# STM32_microcontroller_IOs.net
KiCad netlist of a schematic drawn in Altium Designer
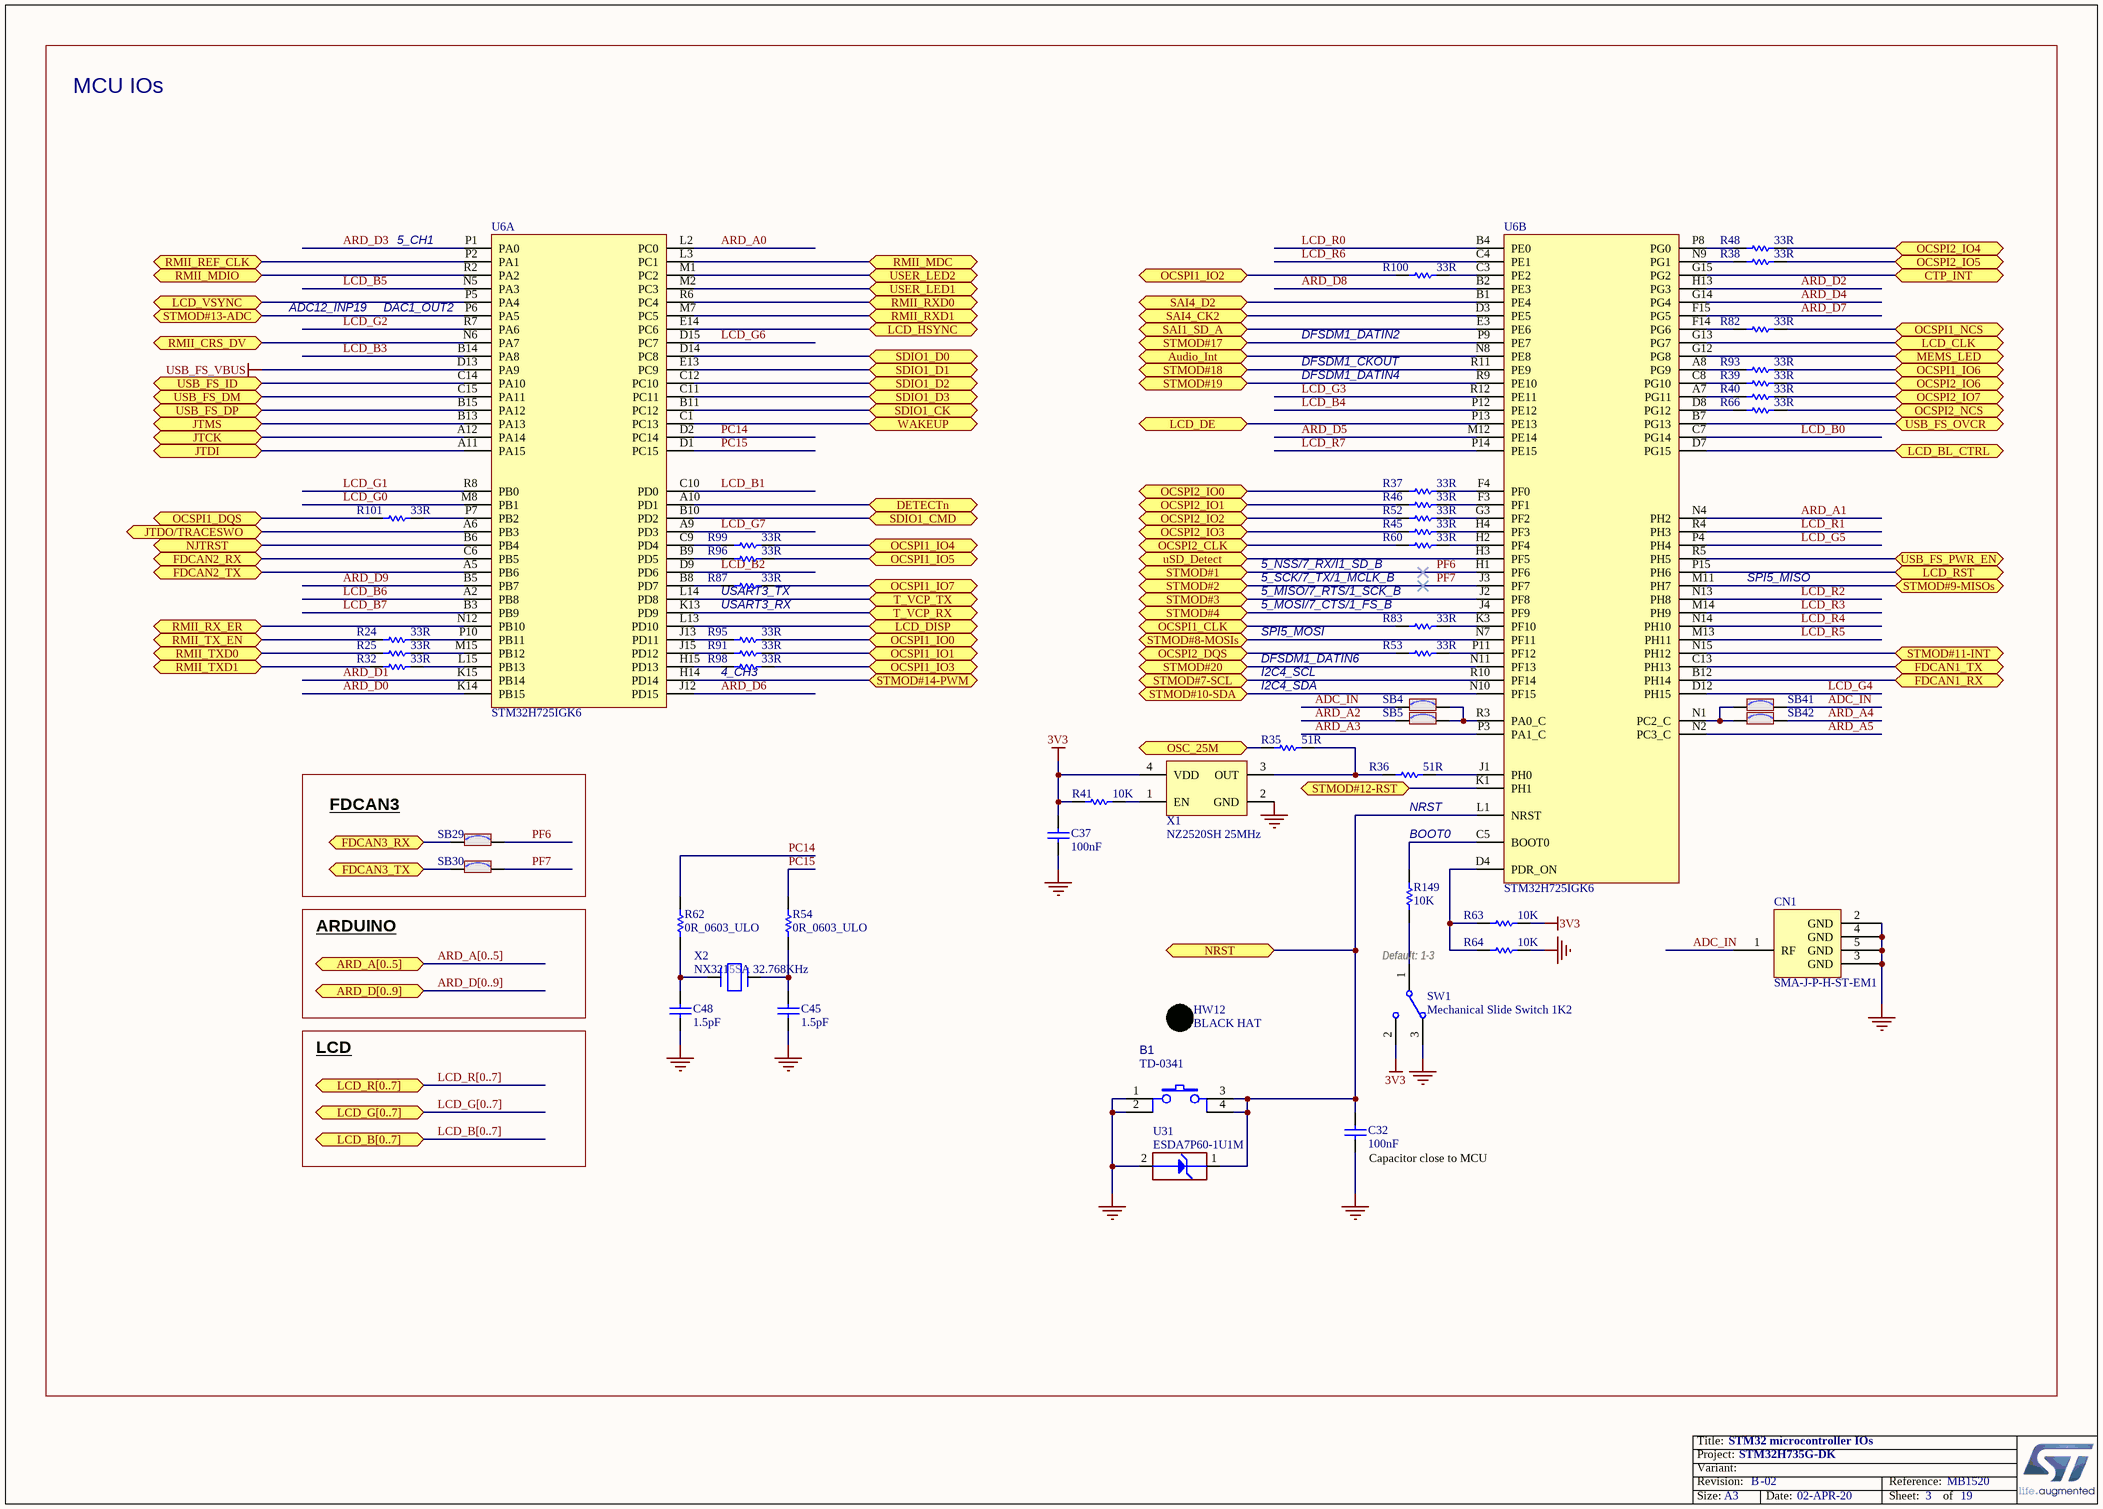
[diagram p0: STM32 microcontroller IOs.SchDoc]

(export (version "E")
  (design (tool "Eeschema 10.0.6"))
  (components
    (comp (ref "B1")
      (value "SW-PUSH-CMS")
      (footprint "SWI_WEALTHMETAL_TD-0341_4P_BLACK")
      (description "Non-Open Push-Button 0.1A 24V BLACK")
      (fields
        (field (name "INTERNAL_PART_NUMBER") "MCD-00001")
        (field (name "MANUFACTURER_PART_NUMBER") "TD-0341")
        (field (name "MANUFACTURER") "WEALTHMETAL")
        (field (name "PROVIDED_BY") "SUBCO")
      )
      (libsource (lib "MCD_PARTS_database") (part "SW-PUSH-CMS"))
    )
    (comp (ref "C32")
      (value "100nF")
      (footprint "C0402")
      (description "Capacitor, MLCC, 100nF, 16V, X7R, 10%, 0402, T=0,5mm")
      (fields
        (field (name "INTERNAL_PART_NUMBER") "MCD-00102")
        (field (name "MANUFACTURER_PART_NUMBER") "CC0402KRX7R7BB104")
        (field (name "PROVIDED_BY") "SUBCO")
      )
      (libsource (lib "MCD_PARTS_database") (part "Capacitor"))
    )
    (comp (ref "C37")
      (value "100nF")
      (footprint "C0402")
      (description "Capacitor, MLCC, 100nF, 16V, X7R, 10%, 0402, T=0,5mm")
      (fields
        (field (name "INTERNAL_PART_NUMBER") "MCD-00102")
        (field (name "MANUFACTURER_PART_NUMBER") "CC0402KRX7R7BB104")
        (field (name "PROVIDED_BY") "SUBCO")
      )
      (libsource (lib "MCD_PARTS_database") (part "Capacitor"))
    )
    (comp (ref "C45")
      (value "1.5pF")
      (footprint "C0402")
      (description "Capacitor, MLCC, 1.5pF, 50V, NPO, +-0.25pF, 0402, T=0,5mm")
      (fields
        (field (name "INTERNAL_PART_NUMBER") "MCD-00563")
        (field (name "MANUFACTURER_PART_NUMBER") "CC0402CRNPO9BN1R5")
        (field (name "PROVIDED_BY") "SUBCO")
      )
      (libsource (lib "MCD_PARTS_database") (part "Capacitor"))
    )
    (comp (ref "C48")
      (value "1.5pF")
      (footprint "C0402")
      (description "Capacitor, MLCC, 1.5pF, 50V, NPO, +-0.25pF, 0402, T=0,5mm")
      (fields
        (field (name "INTERNAL_PART_NUMBER") "MCD-00563")
        (field (name "MANUFACTURER_PART_NUMBER") "CC0402CRNPO9BN1R5")
        (field (name "PROVIDED_BY") "SUBCO")
      )
      (libsource (lib "MCD_PARTS_database") (part "Capacitor"))
    )
    (comp (ref "CN1")
      (value "SMA-J-P-H-ST-EM1")
      (footprint "CON_SAMTEC_SMA-J-P-X-ST-EM1")
      (description "RF SMA connector PCB edge")
      (fields
        (field (name "INTERNAL_PART_NUMBER") "MCD-00279")
        (field (name "MANUFACTURER") "SAMTEC")
        (field (name "PROVIDED_BY") "SUBCO")
      )
      (libsource (lib "MCD_PARTS_database") (part "SMA-J-P-H-ST-EM1"))
    )
    (comp (ref "HW12")
      (value "BLACK HAT")
      (description "Black Hat for switch TD0341X-G01-BLA")
      (fields
        (field (name "INTERNAL_PART_NUMBER") "MCD-00635")
        (field (name "MANUFACTURER_PART_NUMBER") "988.16.09.3.00003_SH-517")
        (field (name "PROVIDED_BY") "SUBCO")
      )
      (libsource (lib "MCD_PARTS_database") (part "BUTTON_HAT_BLACK"))
    )
    (comp (ref "R24")
      (value "33R")
      (footprint "R0402")
      (description "Resistor,33R,0402,1%,1/16W")
      (fields
        (field (name "INTERNAL_PART_NUMBER") "MCD-00455")
        (field (name "MANUFACTURER_PART_NUMBER") "RC0402FR-0733RL")
        (field (name "PROVIDED_BY") "SUBCO")
      )
      (libsource (lib "MCD_PARTS_database") (part "Resistor"))
    )
    (comp (ref "R25")
      (value "33R")
      (footprint "R0402")
      (description "Resistor,33R,0402,1%,1/16W")
      (fields
        (field (name "INTERNAL_PART_NUMBER") "MCD-00455")
        (field (name "MANUFACTURER_PART_NUMBER") "RC0402FR-0733RL")
        (field (name "PROVIDED_BY") "SUBCO")
      )
      (libsource (lib "MCD_PARTS_database") (part "Resistor"))
    )
    (comp (ref "R32")
      (value "33R")
      (footprint "R0402")
      (description "Resistor,33R,0402,1%,1/16W")
      (fields
        (field (name "INTERNAL_PART_NUMBER") "MCD-00455")
        (field (name "MANUFACTURER_PART_NUMBER") "RC0402FR-0733RL")
        (field (name "PROVIDED_BY") "SUBCO")
      )
      (libsource (lib "MCD_PARTS_database") (part "Resistor"))
    )
    (comp (ref "R35")
      (value "51R")
      (footprint "R0402")
      (description "Resistor,51R,0402,1%,1/16W")
      (fields
        (field (name "INTERNAL_PART_NUMBER") "MCD-00485")
        (field (name "MANUFACTURER_PART_NUMBER") "RC0402FR-0751RL")
        (field (name "PROVIDED_BY") "SUBCO")
      )
      (libsource (lib "MCD_PARTS_database") (part "Resistor"))
    )
    (comp (ref "R36")
      (value "51R")
      (footprint "R0402")
      (description "Resistor,51R,0402,1%,1/16W")
      (fields
        (field (name "INTERNAL_PART_NUMBER") "MCD-00485")
        (field (name "MANUFACTURER_PART_NUMBER") "RC0402FR-0751RL")
        (field (name "PROVIDED_BY") "SUBCO")
      )
      (libsource (lib "MCD_PARTS_database") (part "Resistor"))
    )
    (comp (ref "R37")
      (value "33R")
      (footprint "R0402")
      (description "Resistor,33R,0402,1%,1/16W")
      (fields
        (field (name "INTERNAL_PART_NUMBER") "MCD-00455")
        (field (name "MANUFACTURER_PART_NUMBER") "RC0402FR-0733RL")
        (field (name "PROVIDED_BY") "SUBCO")
      )
      (libsource (lib "MCD_PARTS_database") (part "Resistor"))
    )
    (comp (ref "R38")
      (value "33R")
      (footprint "R0402")
      (description "Resistor,33R,0402,1%,1/16W")
      (fields
        (field (name "INTERNAL_PART_NUMBER") "MCD-00455")
        (field (name "MANUFACTURER_PART_NUMBER") "RC0402FR-0733RL")
        (field (name "PROVIDED_BY") "SUBCO")
      )
      (libsource (lib "MCD_PARTS_database") (part "Resistor"))
    )
    (comp (ref "R39")
      (value "33R")
      (footprint "R0402")
      (description "Resistor,33R,0402,1%,1/16W")
      (fields
        (field (name "INTERNAL_PART_NUMBER") "MCD-00455")
        (field (name "MANUFACTURER_PART_NUMBER") "RC0402FR-0733RL")
        (field (name "PROVIDED_BY") "SUBCO")
      )
      (libsource (lib "MCD_PARTS_database") (part "Resistor"))
    )
    (comp (ref "R40")
      (value "33R")
      (footprint "R0402")
      (description "Resistor,33R,0402,1%,1/16W")
      (fields
        (field (name "INTERNAL_PART_NUMBER") "MCD-00455")
        (field (name "MANUFACTURER_PART_NUMBER") "RC0402FR-0733RL")
        (field (name "PROVIDED_BY") "SUBCO")
      )
      (libsource (lib "MCD_PARTS_database") (part "Resistor"))
    )
    (comp (ref "R41")
      (value "10K")
      (footprint "R0402")
      (description "Resistor,10K,0402,1%,1/16W")
      (fields
        (field (name "INTERNAL_PART_NUMBER") "MCD-00053")
        (field (name "MANUFACTURER_PART_NUMBER") "RC0402FR-0710KL")
        (field (name "PROVIDED_BY") "SUBCO")
      )
      (libsource (lib "MCD_PARTS_database") (part "Resistor"))
    )
    (comp (ref "R45")
      (value "33R")
      (footprint "R0402")
      (description "Resistor,33R,0402,1%,1/16W")
      (fields
        (field (name "INTERNAL_PART_NUMBER") "MCD-00455")
        (field (name "MANUFACTURER_PART_NUMBER") "RC0402FR-0733RL")
        (field (name "PROVIDED_BY") "SUBCO")
      )
      (libsource (lib "MCD_PARTS_database") (part "Resistor"))
    )
    (comp (ref "R46")
      (value "33R")
      (footprint "R0402")
      (description "Resistor,33R,0402,1%,1/16W")
      (fields
        (field (name "INTERNAL_PART_NUMBER") "MCD-00455")
        (field (name "MANUFACTURER_PART_NUMBER") "RC0402FR-0733RL")
        (field (name "PROVIDED_BY") "SUBCO")
      )
      (libsource (lib "MCD_PARTS_database") (part "Resistor"))
    )
    (comp (ref "R48")
      (value "33R")
      (footprint "R0402")
      (description "Resistor,33R,0402,1%,1/16W")
      (fields
        (field (name "INTERNAL_PART_NUMBER") "MCD-00455")
        (field (name "MANUFACTURER_PART_NUMBER") "RC0402FR-0733RL")
        (field (name "PROVIDED_BY") "SUBCO")
      )
      (libsource (lib "MCD_PARTS_database") (part "Resistor"))
    )
    (comp (ref "R52")
      (value "33R")
      (footprint "R0402")
      (description "Resistor,33R,0402,1%,1/16W")
      (fields
        (field (name "INTERNAL_PART_NUMBER") "MCD-00455")
        (field (name "MANUFACTURER_PART_NUMBER") "RC0402FR-0733RL")
        (field (name "PROVIDED_BY") "SUBCO")
      )
      (libsource (lib "MCD_PARTS_database") (part "Resistor"))
    )
    (comp (ref "R53")
      (value "33R")
      (footprint "R0402")
      (description "Resistor,33R,0402,1%,1/16W")
      (fields
        (field (name "INTERNAL_PART_NUMBER") "MCD-00455")
        (field (name "MANUFACTURER_PART_NUMBER") "RC0402FR-0733RL")
        (field (name "PROVIDED_BY") "SUBCO")
      )
      (libsource (lib "MCD_PARTS_database") (part "Resistor"))
    )
    (comp (ref "R54")
      (value "0R_0603_ULO")
      (footprint "R0603")
      (description "Resistor,0R,0603,ULO")
      (fields
        (field (name "INTERNAL_PART_NUMBER") "MCD-00181")
        (field (name "MANUFACTURER_PART_NUMBER") "PMR03EZPJ000")
        (field (name "PROVIDED_BY") "SUBCO")
      )
      (libsource (lib "MCD_PARTS_database") (part "Resistor"))
    )
    (comp (ref "R60")
      (value "33R")
      (footprint "R0402")
      (description "Resistor,33R,0402,1%,1/16W")
      (fields
        (field (name "INTERNAL_PART_NUMBER") "MCD-00455")
        (field (name "MANUFACTURER_PART_NUMBER") "RC0402FR-0733RL")
        (field (name "PROVIDED_BY") "SUBCO")
      )
      (libsource (lib "MCD_PARTS_database") (part "Resistor"))
    )
    (comp (ref "R62")
      (value "0R_0603_ULO")
      (footprint "R0603")
      (description "Resistor,0R,0603,ULO")
      (fields
        (field (name "INTERNAL_PART_NUMBER") "MCD-00181")
        (field (name "MANUFACTURER_PART_NUMBER") "PMR03EZPJ000")
        (field (name "PROVIDED_BY") "SUBCO")
      )
      (libsource (lib "MCD_PARTS_database") (part "Resistor"))
    )
    (comp (ref "R63")
      (value "10K")
      (footprint "R0402")
      (description "Resistor,10K,0402,1%,1/16W")
      (fields
        (field (name "INTERNAL_PART_NUMBER") "MCD-00053")
        (field (name "MANUFACTURER_PART_NUMBER") "RC0402FR-0710KL")
        (field (name "PROVIDED_BY") "SUBCO")
      )
      (libsource (lib "MCD_PARTS_database") (part "Resistor"))
    )
    (comp (ref "R64")
      (value "10K")
      (footprint "R0402")
      (description "Resistor,10K,0402,1%,1/16W")
      (fields
        (field (name "INTERNAL_PART_NUMBER") "MCD-00053")
        (field (name "MANUFACTURER_PART_NUMBER") "RC0402FR-0710KL")
        (field (name "PROVIDED_BY") "SUBCO")
      )
      (libsource (lib "MCD_PARTS_database") (part "Resistor"))
    )
    (comp (ref "R66")
      (value "33R")
      (footprint "R0402")
      (description "Resistor,33R,0402,1%,1/16W")
      (fields
        (field (name "INTERNAL_PART_NUMBER") "MCD-00455")
        (field (name "MANUFACTURER_PART_NUMBER") "RC0402FR-0733RL")
        (field (name "PROVIDED_BY") "SUBCO")
      )
      (libsource (lib "MCD_PARTS_database") (part "Resistor"))
    )
    (comp (ref "R82")
      (value "33R")
      (footprint "R0402")
      (description "Resistor,33R,0402,1%,1/16W")
      (fields
        (field (name "INTERNAL_PART_NUMBER") "MCD-00455")
        (field (name "MANUFACTURER_PART_NUMBER") "RC0402FR-0733RL")
        (field (name "PROVIDED_BY") "SUBCO")
      )
      (libsource (lib "MCD_PARTS_database") (part "Resistor"))
    )
    (comp (ref "R83")
      (value "33R")
      (footprint "R0402")
      (description "Resistor,33R,0402,1%,1/16W")
      (fields
        (field (name "INTERNAL_PART_NUMBER") "MCD-00455")
        (field (name "MANUFACTURER_PART_NUMBER") "RC0402FR-0733RL")
        (field (name "PROVIDED_BY") "SUBCO")
      )
      (libsource (lib "MCD_PARTS_database") (part "Resistor"))
    )
    (comp (ref "R87")
      (value "33R")
      (footprint "R0402")
      (description "Resistor,33R,0402,1%,1/16W")
      (fields
        (field (name "INTERNAL_PART_NUMBER") "MCD-00455")
        (field (name "MANUFACTURER_PART_NUMBER") "RC0402FR-0733RL")
        (field (name "PROVIDED_BY") "SUBCO")
      )
      (libsource (lib "MCD_PARTS_database") (part "Resistor"))
    )
    (comp (ref "R91")
      (value "33R")
      (footprint "R0402")
      (description "Resistor,33R,0402,1%,1/16W")
      (fields
        (field (name "INTERNAL_PART_NUMBER") "MCD-00455")
        (field (name "MANUFACTURER_PART_NUMBER") "RC0402FR-0733RL")
        (field (name "PROVIDED_BY") "SUBCO")
      )
      (libsource (lib "MCD_PARTS_database") (part "Resistor"))
    )
    (comp (ref "R93")
      (value "33R")
      (footprint "R0402")
      (description "Resistor,33R,0402,1%,1/16W")
      (fields
        (field (name "INTERNAL_PART_NUMBER") "MCD-00455")
        (field (name "MANUFACTURER_PART_NUMBER") "RC0402FR-0733RL")
        (field (name "PROVIDED_BY") "SUBCO")
      )
      (libsource (lib "MCD_PARTS_database") (part "Resistor"))
    )
    (comp (ref "R95")
      (value "33R")
      (footprint "R0402")
      (description "Resistor,33R,0402,1%,1/16W")
      (fields
        (field (name "INTERNAL_PART_NUMBER") "MCD-00455")
        (field (name "MANUFACTURER_PART_NUMBER") "RC0402FR-0733RL")
        (field (name "PROVIDED_BY") "SUBCO")
      )
      (libsource (lib "MCD_PARTS_database") (part "Resistor"))
    )
    (comp (ref "R96")
      (value "33R")
      (footprint "R0402")
      (description "Resistor,33R,0402,1%,1/16W")
      (fields
        (field (name "INTERNAL_PART_NUMBER") "MCD-00455")
        (field (name "MANUFACTURER_PART_NUMBER") "RC0402FR-0733RL")
        (field (name "PROVIDED_BY") "SUBCO")
      )
      (libsource (lib "MCD_PARTS_database") (part "Resistor"))
    )
    (comp (ref "R98")
      (value "33R")
      (footprint "R0402")
      (description "Resistor,33R,0402,1%,1/16W")
      (fields
        (field (name "INTERNAL_PART_NUMBER") "MCD-00455")
        (field (name "MANUFACTURER_PART_NUMBER") "RC0402FR-0733RL")
        (field (name "PROVIDED_BY") "SUBCO")
      )
      (libsource (lib "MCD_PARTS_database") (part "Resistor"))
    )
    (comp (ref "R99")
      (value "33R")
      (footprint "R0402")
      (description "Resistor,33R,0402,1%,1/16W")
      (fields
        (field (name "INTERNAL_PART_NUMBER") "MCD-00455")
        (field (name "MANUFACTURER_PART_NUMBER") "RC0402FR-0733RL")
        (field (name "PROVIDED_BY") "SUBCO")
      )
      (libsource (lib "MCD_PARTS_database") (part "Resistor"))
    )
    (comp (ref "R100")
      (value "33R")
      (footprint "R0402")
      (description "Resistor,33R,0402,1%,1/16W")
      (fields
        (field (name "INTERNAL_PART_NUMBER") "MCD-00455")
        (field (name "MANUFACTURER_PART_NUMBER") "RC0402FR-0733RL")
        (field (name "PROVIDED_BY") "SUBCO")
      )
      (libsource (lib "MCD_PARTS_database") (part "Resistor"))
    )
    (comp (ref "R101")
      (value "33R")
      (footprint "R0402")
      (description "Resistor,33R,0402,1%,1/16W")
      (fields
        (field (name "INTERNAL_PART_NUMBER") "MCD-00455")
        (field (name "MANUFACTURER_PART_NUMBER") "RC0402FR-0733RL")
        (field (name "PROVIDED_BY") "SUBCO")
      )
      (libsource (lib "MCD_PARTS_database") (part "Resistor"))
    )
    (comp (ref "R149")
      (value "10K")
      (footprint "R0402")
      (description "Resistor,10K,0402,1%,1/16W")
      (fields
        (field (name "INTERNAL_PART_NUMBER") "MCD-00053")
        (field (name "MANUFACTURER_PART_NUMBER") "RC0402FR-0710KL")
        (field (name "PROVIDED_BY") "SUBCO")
      )
      (libsource (lib "MCD_PARTS_database") (part "Resistor"))
    )
    (comp (ref "SB4")
      (value "SB_ON")
      (footprint "SOLDER-BRIDGE_R0603-0R")
      (description "Solder Bridge ON")
      (fields
        (field (name "INTERNAL_PART_NUMBER") "MCD-00071")
        (field (name "MANUFACTURER_PART_NUMBER") "RC0603JR-070RL")
        (field (name "PROVIDED_BY") "SUBCO")
      )
      (libsource (lib "MCD_PARTS_database") (part "SB_ON"))
    )
    (comp (ref "SB5")
      (value "SB_ON")
      (footprint "SOLDER-BRIDGE_R0603-0R")
      (description "Solder Bridge ON")
      (fields
        (field (name "INTERNAL_PART_NUMBER") "MCD-00071")
        (field (name "MANUFACTURER_PART_NUMBER") "RC0603JR-070RL")
        (field (name "PROVIDED_BY") "SUBCO")
      )
      (libsource (lib "MCD_PARTS_database") (part "SB_ON"))
    )
    (comp (ref "SB29")
      (value "SB_ON")
      (footprint "SOLDER-BRIDGE_R0603-0R")
      (description "Solder Bridge ON")
      (fields
        (field (name "INTERNAL_PART_NUMBER") "MCD-00071")
        (field (name "MANUFACTURER_PART_NUMBER") "RC0603JR-070RL")
        (field (name "PROVIDED_BY") "SUBCO")
      )
      (libsource (lib "MCD_PARTS_database") (part "SB_ON"))
    )
    (comp (ref "SB30")
      (value "SB_ON")
      (footprint "SOLDER-BRIDGE_R0603-0R")
      (description "Solder Bridge ON")
      (fields
        (field (name "INTERNAL_PART_NUMBER") "MCD-00071")
        (field (name "MANUFACTURER_PART_NUMBER") "RC0603JR-070RL")
        (field (name "PROVIDED_BY") "SUBCO")
      )
      (libsource (lib "MCD_PARTS_database") (part "SB_ON"))
    )
    (comp (ref "SB41")
      (value "SB_ON")
      (footprint "SOLDER-BRIDGE_R0603-0R")
      (description "Solder Bridge ON")
      (fields
        (field (name "INTERNAL_PART_NUMBER") "MCD-00071")
        (field (name "MANUFACTURER_PART_NUMBER") "RC0603JR-070RL")
        (field (name "PROVIDED_BY") "SUBCO")
      )
      (libsource (lib "MCD_PARTS_database") (part "SB_ON"))
    )
    (comp (ref "SB42")
      (value "SB_ON")
      (footprint "SOLDER-BRIDGE_R0603-0R")
      (description "Solder Bridge ON")
      (fields
        (field (name "INTERNAL_PART_NUMBER") "MCD-00071")
        (field (name "MANUFACTURER_PART_NUMBER") "RC0603JR-070RL")
        (field (name "PROVIDED_BY") "SUBCO")
      )
      (libsource (lib "MCD_PARTS_database") (part "SB_ON"))
    )
    (comp (ref "SW1")
      (value "Mechanical Slide Switch 1K2")
      (footprint "SWI_EAO_09-03290-01_EXTENDED_STRAIGHT_BLACK")
      (description "Mechanical Slide Switches 1K2 BLK ACT GOLD STRT MNT")
      (fields
        (field (name "INTERNAL_PART_NUMBER") "MCD-00566")
        (field (name "MANUFACTURER_PART_NUMBER") "09.03290.01")
        (field (name "PROVIDED_BY") "SUBCO")
      )
      (libsource (lib "MCD_PARTS_database") (part "SW_MECA_1K2"))
    )
    (comp (ref "U6")
      (value "STM32H725IGK6")
      (footprint "ICC_UFBGA201_176+25_10X10_P065")
      (description "STM32H725IGK6 MCU, Cut1.0, 10x10x0.6mm, Pitch0.65mm, Int SMPS")
      (fields
        (field (name "INTERNAL_PART_NUMBER") "MCD-01673")
        (field (name "MANUFACTURER") "STMICROELECTRONICS")
        (field (name "PROVIDED_BY") "SUBCO with ST control")
      )
      (libsource (lib "MCD_PARTS_database") (part "STM32H725IGK6U"))
    )
    (comp (ref "U31")
      (value "ESDA7P60-1U1M")
      (footprint "ESD_QFN2_1P6X1_P125")
      (description "High power transient voltage suppressor, 7V breakdown")
      (fields
        (field (name "INTERNAL_PART_NUMBER") "MCD-00251")
        (field (name "MANUFACTURER") "STMICROELECTRONICS")
        (field (name "PROVIDED_BY") "SUBCO with ST control")
      )
      (libsource (lib "MCD_PARTS_database") (part "ESD-TRANSIL"))
    )
    (comp (ref "X1")
      (value "NZ2520SH 25MHz")
      (footprint "OSC_NDK_NZ2520SB_4P")
      (description "Oscillator 25Mhz, +-50ppm, Vcc:3.3V typ, square wave: [0.1Vcc;0.9Vcc], Enable pin, SMD")
      (fields
        (field (name "INTERNAL_PART_NUMBER") "MCD-00597")
        (field (name "MANUFACTURER_PART_NUMBER") "NZ2520SH 25MHz END4869C")
        (field (name "PROVIDED_BY") "SUBCO")
      )
      (libsource (lib "MCD_PARTS_database") (part "OSCILLATOR_4_PINS"))
    )
    (comp (ref "X2")
      (value "NX3215SA 32.768KHz")
      (footprint "CRY_NX3215SA_2P")
      (description "Crystal 32.768kHz, 6pF, +-20ppm, 50Kohms max, SMD")
      (fields
        (field (name "INTERNAL_PART_NUMBER") "MCD-00091")
        (field (name "MANUFACTURER_PART_NUMBER") "NX3215SA 32.768KHz EXS00A-MU00525")
        (field (name "PROVIDED_BY") "SUBCO")
      )
      (libsource (lib "MCD_PARTS_database") (part "XTAL_2_PINS"))
    )
  )
  (nets
    (net (code "1") (name "/ADC_IN") (class "Default")
      (node (ref "CN1") (pin "1") (pinfunction "RF_1") (pintype "passive"))
      (node (ref "SB4") (pin "1") (pinfunction "1_1") (pintype "passive"))
      (node (ref "SB41") (pin "2") (pinfunction "2_2") (pintype "passive"))
    )
    (net (code "2") (name "/ARD_A0") (class "Default")
      (node (ref "U6") (pin "L2") (pinfunction "PC0_L2") (pintype "passive"))
    )
    (net (code "3") (name "/ARD_A1") (class "Default")
      (node (ref "U6") (pin "N4") (pinfunction "PH2_N4") (pintype "passive"))
    )
    (net (code "4") (name "/ARD_A2") (class "Default")
      (node (ref "SB5") (pin "1") (pinfunction "1_1") (pintype "passive"))
    )
    (net (code "5") (name "/ARD_A3") (class "Default")
      (node (ref "U6") (pin "P3") (pinfunction "PA1_C_P3") (pintype "passive"))
    )
    (net (code "6") (name "/ARD_A4") (class "Default")
      (node (ref "SB42") (pin "2") (pinfunction "2_2") (pintype "passive"))
    )
    (net (code "7") (name "/ARD_A5") (class "Default")
      (node (ref "U6") (pin "N2") (pinfunction "PC3_C_N2") (pintype "passive"))
    )
    (net (code "9") (name "/ARD_D0") (class "Default")
      (node (ref "U6") (pin "K14") (pinfunction "PB15_K14") (pintype "passive"))
    )
    (net (code "10") (name "/ARD_D1") (class "Default")
      (node (ref "U6") (pin "K15") (pinfunction "PB14_K15") (pintype "passive"))
    )
    (net (code "11") (name "/ARD_D2") (class "Default")
      (node (ref "U6") (pin "H13") (pinfunction "PG3_H13") (pintype "passive"))
    )
    (net (code "12") (name "/ARD_D3") (class "Default")
      (node (ref "U6") (pin "P1") (pinfunction "PA0_P1") (pintype "passive"))
    )
    (net (code "13") (name "/ARD_D4") (class "Default")
      (node (ref "U6") (pin "G14") (pinfunction "PG4_G14") (pintype "passive"))
    )
    (net (code "14") (name "/ARD_D5") (class "Default")
      (node (ref "U6") (pin "M12") (pinfunction "PE14_M12") (pintype "passive"))
    )
    (net (code "15") (name "/ARD_D6") (class "Default")
      (node (ref "U6") (pin "J12") (pinfunction "PD15_J12") (pintype "passive"))
    )
    (net (code "16") (name "/ARD_D7") (class "Default")
      (node (ref "U6") (pin "F15") (pinfunction "PG5_F15") (pintype "passive"))
    )
    (net (code "17") (name "/ARD_D8") (class "Default")
      (node (ref "U6") (pin "B2") (pinfunction "PE3_B2") (pintype "passive"))
    )
    (net (code "18") (name "/ARD_D9") (class "Default")
      (node (ref "U6") (pin "B5") (pinfunction "PB7_B5") (pintype "passive"))
    )
    (net (code "20") (name "/Audio_Int") (class "Default")
      (node (ref "U6") (pin "N8") (pinfunction "PE8_N8") (pintype "passive"))
    )
    (net (code "21") (name "/CTP_INT") (class "Default")
      (node (ref "U6") (pin "G15") (pinfunction "PG2_G15") (pintype "passive"))
    )
    (net (code "22") (name "/DETECTn") (class "Default")
      (node (ref "U6") (pin "A10") (pinfunction "PD1_A10") (pintype "passive"))
    )
    (net (code "23") (name "/FDCAN1_RX") (class "Default")
      (node (ref "U6") (pin "B12") (pinfunction "PH14_B12") (pintype "passive"))
    )
    (net (code "24") (name "/FDCAN1_TX") (class "Default")
      (node (ref "U6") (pin "C13") (pinfunction "PH13_C13") (pintype "passive"))
    )
    (net (code "25") (name "/FDCAN2_RX") (class "Default")
      (node (ref "U6") (pin "C6") (pinfunction "PB5_C6") (pintype "passive"))
    )
    (net (code "26") (name "/FDCAN2_TX") (class "Default")
      (node (ref "U6") (pin "A5") (pinfunction "PB6_A5") (pintype "passive"))
    )
    (net (code "27") (name "/FDCAN3_RX") (class "Default")
      (node (ref "SB29") (pin "1") (pinfunction "1_1") (pintype "passive"))
    )
    (net (code "28") (name "/FDCAN3_TX") (class "Default")
      (node (ref "SB30") (pin "1") (pinfunction "1_1") (pintype "passive"))
    )
    (net (code "29") (name "/JTCK") (class "Default")
      (node (ref "U6") (pin "A12") (pinfunction "PA14_A12") (pintype "passive"))
    )
    (net (code "30") (name "/JTDI") (class "Default")
      (node (ref "U6") (pin "A11") (pinfunction "PA15_A11") (pintype "passive"))
    )
    (net (code "31") (name "/JTDO{slash}TRACESWO") (class "Default")
      (node (ref "U6") (pin "A6") (pinfunction "PB3_A6") (pintype "passive"))
    )
    (net (code "32") (name "/JTMS") (class "Default")
      (node (ref "U6") (pin "B13") (pinfunction "PA13_B13") (pintype "passive"))
    )
    (net (code "33") (name "/LCD_B0") (class "Default")
      (node (ref "U6") (pin "C7") (pinfunction "PG14_C7") (pintype "passive"))
    )
    (net (code "34") (name "/LCD_B1") (class "Default")
      (node (ref "U6") (pin "C10") (pinfunction "PD0_C10") (pintype "passive"))
    )
    (net (code "35") (name "/LCD_B2") (class "Default")
      (node (ref "U6") (pin "D9") (pinfunction "PD6_D9") (pintype "passive"))
    )
    (net (code "36") (name "/LCD_B3") (class "Default")
      (node (ref "U6") (pin "B14") (pinfunction "PA8_B14") (pintype "passive"))
    )
    (net (code "37") (name "/LCD_B4") (class "Default")
      (node (ref "U6") (pin "P12") (pinfunction "PE12_P12") (pintype "passive"))
    )
    (net (code "38") (name "/LCD_B5") (class "Default")
      (node (ref "U6") (pin "N5") (pinfunction "PA3_N5") (pintype "passive"))
    )
    (net (code "39") (name "/LCD_B6") (class "Default")
      (node (ref "U6") (pin "A2") (pinfunction "PB8_A2") (pintype "passive"))
    )
    (net (code "40") (name "/LCD_B7") (class "Default")
      (node (ref "U6") (pin "B3") (pinfunction "PB9_B3") (pintype "passive"))
    )
    (net (code "41") (name "/LCD_BL_CTRL") (class "Default")
      (node (ref "U6") (pin "D7") (pinfunction "PG15_D7") (pintype "passive"))
    )
    (net (code "43") (name "/LCD_CLK") (class "Default")
      (node (ref "U6") (pin "G13") (pinfunction "PG7_G13") (pintype "passive"))
    )
    (net (code "44") (name "/LCD_DE") (class "Default")
      (node (ref "U6") (pin "P13") (pinfunction "PE13_P13") (pintype "passive"))
    )
    (net (code "45") (name "/LCD_DISP") (class "Default")
      (node (ref "U6") (pin "L13") (pinfunction "PD10_L13") (pintype "passive"))
    )
    (net (code "46") (name "/LCD_G0") (class "Default")
      (node (ref "U6") (pin "M8") (pinfunction "PB1_M8") (pintype "passive"))
    )
    (net (code "47") (name "/LCD_G1") (class "Default")
      (node (ref "U6") (pin "R8") (pinfunction "PB0_R8") (pintype "passive"))
    )
    (net (code "48") (name "/LCD_G2") (class "Default")
      (node (ref "U6") (pin "R7") (pinfunction "PA6_R7") (pintype "passive"))
    )
    (net (code "49") (name "/LCD_G3") (class "Default")
      (node (ref "U6") (pin "R12") (pinfunction "PE11_R12") (pintype "passive"))
    )
    (net (code "50") (name "/LCD_G4") (class "Default")
      (node (ref "U6") (pin "D12") (pinfunction "PH15_D12") (pintype "passive"))
    )
    (net (code "51") (name "/LCD_G5") (class "Default")
      (node (ref "U6") (pin "P4") (pinfunction "PH4_P4") (pintype "passive"))
    )
    (net (code "52") (name "/LCD_G6") (class "Default")
      (node (ref "U6") (pin "D15") (pinfunction "PC7_D15") (pintype "passive"))
    )
    (net (code "53") (name "/LCD_G7") (class "Default")
      (node (ref "U6") (pin "A9") (pinfunction "PD3_A9") (pintype "passive"))
    )
    (net (code "55") (name "/LCD_HSYNC") (class "Default")
      (node (ref "U6") (pin "E14") (pinfunction "PC6_E14") (pintype "passive"))
    )
    (net (code "56") (name "/LCD_R0") (class "Default")
      (node (ref "U6") (pin "B4") (pinfunction "PE0_B4") (pintype "passive"))
    )
    (net (code "57") (name "/LCD_R1") (class "Default")
      (node (ref "U6") (pin "R4") (pinfunction "PH3_R4") (pintype "passive"))
    )
    (net (code "58") (name "/LCD_R2") (class "Default")
      (node (ref "U6") (pin "N13") (pinfunction "PH8_N13") (pintype "passive"))
    )
    (net (code "59") (name "/LCD_R3") (class "Default")
      (node (ref "U6") (pin "M14") (pinfunction "PH9_M14") (pintype "passive"))
    )
    (net (code "60") (name "/LCD_R4") (class "Default")
      (node (ref "U6") (pin "N14") (pinfunction "PH10_N14") (pintype "passive"))
    )
    (net (code "61") (name "/LCD_R5") (class "Default")
      (node (ref "U6") (pin "M13") (pinfunction "PH11_M13") (pintype "passive"))
    )
    (net (code "62") (name "/LCD_R6") (class "Default")
      (node (ref "U6") (pin "C4") (pinfunction "PE1_C4") (pintype "passive"))
    )
    (net (code "63") (name "/LCD_R7") (class "Default")
      (node (ref "U6") (pin "P14") (pinfunction "PE15_P14") (pintype "passive"))
    )
    (net (code "64") (name "/LCD_RST") (class "Default")
      (node (ref "U6") (pin "P15") (pinfunction "PH6_P15") (pintype "passive"))
    )
    (net (code "66") (name "/LCD_VSYNC") (class "Default")
      (node (ref "U6") (pin "P5") (pinfunction "PA4_P5") (pintype "passive"))
    )
    (net (code "67") (name "/MEMS_LED") (class "Default")
      (node (ref "U6") (pin "G12") (pinfunction "PG8_G12") (pintype "passive"))
    )
    (net (code "68") (name "/NJTRST") (class "Default")
      (node (ref "U6") (pin "B6") (pinfunction "PB4_B6") (pintype "passive"))
    )
    (net (code "69") (name "/NRST") (class "Default")
      (node (ref "B1") (pin "3") (pinfunction "3_3") (pintype "passive"))
      (node (ref "B1") (pin "4") (pinfunction "4_4") (pintype "passive"))
      (node (ref "C32") (pin "2") (pinfunction "2_2") (pintype "passive"))
      (node (ref "U31") (pin "1") (pinfunction "IO1_1") (pintype "passive"))
      (node (ref "U6") (pin "L1") (pinfunction "NRST_L1") (pintype "passive"))
    )
    (net (code "70") (name "/OCSPI1_CLK") (class "Default")
      (node (ref "R83") (pin "1") (pinfunction "1_1") (pintype "passive"))
    )
    (net (code "71") (name "/OCSPI1_DQS") (class "Default")
      (node (ref "R101") (pin "1") (pinfunction "1_1") (pintype "passive"))
    )
    (net (code "72") (name "/OCSPI1_IO0") (class "Default")
      (node (ref "R95") (pin "2") (pinfunction "2_2") (pintype "passive"))
    )
    (net (code "73") (name "/OCSPI1_IO1") (class "Default")
      (node (ref "R91") (pin "2") (pinfunction "2_2") (pintype "passive"))
    )
    (net (code "74") (name "/OCSPI1_IO2") (class "Default")
      (node (ref "R100") (pin "1") (pinfunction "1_1") (pintype "passive"))
    )
    (net (code "75") (name "/OCSPI1_IO3") (class "Default")
      (node (ref "R98") (pin "2") (pinfunction "2_2") (pintype "passive"))
    )
    (net (code "76") (name "/OCSPI1_IO4") (class "Default")
      (node (ref "R99") (pin "2") (pinfunction "2_2") (pintype "passive"))
    )
    (net (code "77") (name "/OCSPI1_IO5") (class "Default")
      (node (ref "R96") (pin "2") (pinfunction "2_2") (pintype "passive"))
    )
    (net (code "78") (name "/OCSPI1_IO6") (class "Default")
      (node (ref "R93") (pin "2") (pinfunction "2_2") (pintype "passive"))
    )
    (net (code "79") (name "/OCSPI1_IO7") (class "Default")
      (node (ref "R87") (pin "2") (pinfunction "2_2") (pintype "passive"))
    )
    (net (code "80") (name "/OCSPI1_NCS") (class "Default")
      (node (ref "R82") (pin "2") (pinfunction "2_2") (pintype "passive"))
    )
    (net (code "81") (name "/OCSPI2_CLK") (class "Default")
      (node (ref "R60") (pin "1") (pinfunction "1_1") (pintype "passive"))
    )
    (net (code "82") (name "/OCSPI2_DQS") (class "Default")
      (node (ref "R53") (pin "1") (pinfunction "1_1") (pintype "passive"))
    )
    (net (code "83") (name "/OCSPI2_IO0") (class "Default")
      (node (ref "R37") (pin "1") (pinfunction "1_1") (pintype "passive"))
    )
    (net (code "84") (name "/OCSPI2_IO1") (class "Default")
      (node (ref "R46") (pin "1") (pinfunction "1_1") (pintype "passive"))
    )
    (net (code "85") (name "/OCSPI2_IO2") (class "Default")
      (node (ref "R52") (pin "1") (pinfunction "1_1") (pintype "passive"))
    )
    (net (code "86") (name "/OCSPI2_IO3") (class "Default")
      (node (ref "R45") (pin "1") (pinfunction "1_1") (pintype "passive"))
    )
    (net (code "87") (name "/OCSPI2_IO4") (class "Default")
      (node (ref "R48") (pin "2") (pinfunction "2_2") (pintype "passive"))
    )
    (net (code "88") (name "/OCSPI2_IO5") (class "Default")
      (node (ref "R38") (pin "2") (pinfunction "2_2") (pintype "passive"))
    )
    (net (code "89") (name "/OCSPI2_IO6") (class "Default")
      (node (ref "R39") (pin "2") (pinfunction "2_2") (pintype "passive"))
    )
    (net (code "90") (name "/OCSPI2_IO7") (class "Default")
      (node (ref "R40") (pin "2") (pinfunction "2_2") (pintype "passive"))
    )
    (net (code "91") (name "/OCSPI2_NCS") (class "Default")
      (node (ref "R66") (pin "2") (pinfunction "2_2") (pintype "passive"))
    )
    (net (code "92") (name "/OSC_25M") (class "Default")
      (node (ref "R35") (pin "1") (pinfunction "1_1") (pintype "passive"))
    )
    (net (code "93") (name "/PC14") (class "Default")
      (node (ref "R62") (pin "1") (pinfunction "1_1") (pintype "passive"))
      (node (ref "U6") (pin "D2") (pinfunction "PC14_D2") (pintype "passive"))
    )
    (net (code "94") (name "/PC15") (class "Default")
      (node (ref "R54") (pin "1") (pinfunction "1_1") (pintype "passive"))
      (node (ref "U6") (pin "D1") (pinfunction "PC15_D1") (pintype "passive"))
    )
    (net (code "95") (name "/PF6") (class "Default")
      (node (ref "SB29") (pin "2") (pinfunction "2_2") (pintype "passive"))
      (node (ref "U6") (pin "H1") (pinfunction "PF6_H1") (pintype "passive"))
    )
    (net (code "96") (name "/PF7") (class "Default")
      (node (ref "SB30") (pin "2") (pinfunction "2_2") (pintype "passive"))
      (node (ref "U6") (pin "J3") (pinfunction "PF7_J3") (pintype "passive"))
    )
    (net (code "97") (name "/RMII_CRS_DV") (class "Default")
      (node (ref "U6") (pin "N6") (pinfunction "PA7_N6") (pintype "passive"))
    )
    (net (code "98") (name "/RMII_MDC") (class "Default")
      (node (ref "U6") (pin "L3") (pinfunction "PC1_L3") (pintype "passive"))
    )
    (net (code "99") (name "/RMII_MDIO") (class "Default")
      (node (ref "U6") (pin "R2") (pinfunction "PA2_R2") (pintype "passive"))
    )
    (net (code "100") (name "/RMII_REF_CLK") (class "Default")
      (node (ref "U6") (pin "P2") (pinfunction "PA1_P2") (pintype "passive"))
    )
    (net (code "101") (name "/RMII_RXD0") (class "Default")
      (node (ref "U6") (pin "R6") (pinfunction "PC4_R6") (pintype "passive"))
    )
    (net (code "102") (name "/RMII_RXD1") (class "Default")
      (node (ref "U6") (pin "M7") (pinfunction "PC5_M7") (pintype "passive"))
    )
    (net (code "103") (name "/RMII_RX_ER") (class "Default")
      (node (ref "U6") (pin "N12") (pinfunction "PB10_N12") (pintype "passive"))
    )
    (net (code "104") (name "/RMII_TXD0") (class "Default")
      (node (ref "R25") (pin "1") (pinfunction "1_1") (pintype "passive"))
    )
    (net (code "105") (name "/RMII_TXD1") (class "Default")
      (node (ref "R32") (pin "1") (pinfunction "1_1") (pintype "passive"))
    )
    (net (code "106") (name "/RMII_TX_EN") (class "Default")
      (node (ref "R24") (pin "1") (pinfunction "1_1") (pintype "passive"))
    )
    (net (code "107") (name "/SAI1_SD_A") (class "Default")
      (node (ref "U6") (pin "E3") (pinfunction "PE6_E3") (pintype "passive"))
    )
    (net (code "108") (name "/SAI4_CK2") (class "Default")
      (node (ref "U6") (pin "D3") (pinfunction "PE5_D3") (pintype "passive"))
    )
    (net (code "109") (name "/SAI4_D2") (class "Default")
      (node (ref "U6") (pin "B1") (pinfunction "PE4_B1") (pintype "passive"))
    )
    (net (code "110") (name "/SDIO1_CK") (class "Default")
      (node (ref "U6") (pin "B11") (pinfunction "PC12_B11") (pintype "passive"))
    )
    (net (code "111") (name "/SDIO1_CMD") (class "Default")
      (node (ref "U6") (pin "B10") (pinfunction "PD2_B10") (pintype "passive"))
    )
    (net (code "112") (name "/SDIO1_D0") (class "Default")
      (node (ref "U6") (pin "D14") (pinfunction "PC8_D14") (pintype "passive"))
    )
    (net (code "113") (name "/SDIO1_D1") (class "Default")
      (node (ref "U6") (pin "E13") (pinfunction "PC9_E13") (pintype "passive"))
    )
    (net (code "114") (name "/SDIO1_D2") (class "Default")
      (node (ref "U6") (pin "C12") (pinfunction "PC10_C12") (pintype "passive"))
    )
    (net (code "115") (name "/SDIO1_D3") (class "Default")
      (node (ref "U6") (pin "C11") (pinfunction "PC11_C11") (pintype "passive"))
    )
    (net (code "116") (name "/STMOD#3") (class "Default")
      (node (ref "U6") (pin "J2") (pinfunction "PF8_J2") (pintype "passive"))
    )
    (net (code "117") (name "/STMOD#4") (class "Default")
      (node (ref "U6") (pin "J4") (pinfunction "PF9_J4") (pintype "passive"))
    )
    (net (code "118") (name "/STMOD#7-SCL") (class "Default")
      (node (ref "U6") (pin "R10") (pinfunction "PF14_R10") (pintype "passive"))
    )
    (net (code "119") (name "/STMOD#8-MOSIs") (class "Default")
      (node (ref "U6") (pin "N7") (pinfunction "PF11_N7") (pintype "passive"))
    )
    (net (code "120") (name "/STMOD#9-MISOs") (class "Default")
      (node (ref "U6") (pin "M11") (pinfunction "PH7_M11") (pintype "passive"))
    )
    (net (code "121") (name "/STMOD#10-SDA") (class "Default")
      (node (ref "U6") (pin "N10") (pinfunction "PF15_N10") (pintype "passive"))
    )
    (net (code "122") (name "/STMOD#11-INT") (class "Default")
      (node (ref "U6") (pin "N15") (pinfunction "PH12_N15") (pintype "passive"))
    )
    (net (code "123") (name "/STMOD#12-RST") (class "Default")
      (node (ref "U6") (pin "K1") (pinfunction "PH1_K1") (pintype "passive"))
    )
    (net (code "124") (name "/STMOD#13-ADC") (class "Default")
      (node (ref "U6") (pin "P6") (pinfunction "PA5_P6") (pintype "passive"))
    )
    (net (code "125") (name "/STMOD#14-PWM") (class "Default")
      (node (ref "U6") (pin "H14") (pinfunction "PD14_H14") (pintype "passive"))
    )
    (net (code "126") (name "/STMOD#17") (class "Default")
      (node (ref "U6") (pin "P9") (pinfunction "PE7_P9") (pintype "passive"))
    )
    (net (code "127") (name "/STMOD#18") (class "Default")
      (node (ref "U6") (pin "R11") (pinfunction "PE9_R11") (pintype "passive"))
    )
    (net (code "128") (name "/STMOD#19") (class "Default")
      (node (ref "U6") (pin "R9") (pinfunction "PE10_R9") (pintype "passive"))
    )
    (net (code "129") (name "/STMOD#20") (class "Default")
      (node (ref "U6") (pin "N11") (pinfunction "PF13_N11") (pintype "passive"))
    )
    (net (code "130") (name "/T_VCP_RX") (class "Default")
      (node (ref "U6") (pin "K13") (pinfunction "PD9_K13") (pintype "passive"))
    )
    (net (code "131") (name "/T_VCP_TX") (class "Default")
      (node (ref "U6") (pin "L14") (pinfunction "PD8_L14") (pintype "passive"))
    )
    (net (code "132") (name "/USB_FS_DM") (class "Default")
      (node (ref "U6") (pin "C15") (pinfunction "PA11_C15") (pintype "passive"))
    )
    (net (code "133") (name "/USB_FS_DP") (class "Default")
      (node (ref "U6") (pin "B15") (pinfunction "PA12_B15") (pintype "passive"))
    )
    (net (code "134") (name "/USB_FS_ID") (class "Default")
      (node (ref "U6") (pin "C14") (pinfunction "PA10_C14") (pintype "passive"))
    )
    (net (code "135") (name "/USB_FS_OVCR") (class "Default")
      (node (ref "U6") (pin "B7") (pinfunction "PG13_B7") (pintype "passive"))
    )
    (net (code "136") (name "/USB_FS_PWR_EN") (class "Default")
      (node (ref "U6") (pin "R5") (pinfunction "PH5_R5") (pintype "passive"))
    )
    (net (code "137") (name "/USER_LED1") (class "Default")
      (node (ref "U6") (pin "M2") (pinfunction "PC3_M2") (pintype "passive"))
    )
    (net (code "138") (name "/USER_LED2") (class "Default")
      (node (ref "U6") (pin "M1") (pinfunction "PC2_M1") (pintype "passive"))
    )
    (net (code "139") (name "/WAKEUP") (class "Default")
      (node (ref "U6") (pin "C1") (pinfunction "PC13_C1") (pintype "passive"))
    )
    (net (code "140") (name "/uSD_Detect") (class "Default")
      (node (ref "U6") (pin "H3") (pinfunction "PF5_H3") (pintype "passive"))
    )
    (net (code "141") (name "3V3") (class "Default")
      (node (ref "C37") (pin "2") (pinfunction "2_2") (pintype "passive"))
      (node (ref "R41") (pin "2") (pinfunction "2_2") (pintype "passive"))
      (node (ref "R63") (pin "1") (pinfunction "1_1") (pintype "passive"))
      (node (ref "SW1") (pin "2") (pintype "passive"))
      (node (ref "X1") (pin "4") (pinfunction "VDD_4") (pintype "passive"))
    )
    (net (code "142") (name "GND") (class "Default")
      (node (ref "B1") (pin "1") (pinfunction "1_1") (pintype "passive"))
      (node (ref "B1") (pin "2") (pinfunction "2_2") (pintype "passive"))
      (node (ref "C32") (pin "1") (pinfunction "1_1") (pintype "passive"))
      (node (ref "C37") (pin "1") (pinfunction "1_1") (pintype "passive"))
      (node (ref "C45") (pin "1") (pinfunction "1_1") (pintype "passive"))
      (node (ref "C48") (pin "1") (pinfunction "1_1") (pintype "passive"))
      (node (ref "CN1") (pin "2") (pinfunction "GND_2") (pintype "passive"))
      (node (ref "CN1") (pin "3") (pinfunction "GND_3") (pintype "passive"))
      (node (ref "CN1") (pin "4") (pinfunction "GND_4") (pintype "passive"))
      (node (ref "CN1") (pin "5") (pinfunction "GND_5") (pintype "passive"))
      (node (ref "R64") (pin "1") (pinfunction "1_1") (pintype "passive"))
      (node (ref "SW1") (pin "3") (pintype "passive"))
      (node (ref "U31") (pin "2") (pinfunction "GND_2") (pintype "passive"))
      (node (ref "X1") (pin "2") (pinfunction "GND_2") (pintype "passive"))
    )
    (net (code "143") (name "Net-(R149-Pad2)") (class "Default")
      (node (ref "R149") (pin "2") (pinfunction "2_2") (pintype "passive"))
      (node (ref "SW1") (pin "1") (pintype "passive"))
    )
    (net (code "144") (name "Net-(U6A-PB2)") (class "Default")
      (node (ref "R101") (pin "2") (pinfunction "2_2") (pintype "passive"))
      (node (ref "U6") (pin "P7") (pinfunction "PB2_P7") (pintype "passive"))
    )
    (net (code "145") (name "Net-(U6A-PB11)") (class "Default")
      (node (ref "R24") (pin "2") (pinfunction "2_2") (pintype "passive"))
      (node (ref "U6") (pin "P10") (pinfunction "PB11_P10") (pintype "passive"))
    )
    (net (code "146") (name "Net-(U6A-PB12)") (class "Default")
      (node (ref "R25") (pin "2") (pinfunction "2_2") (pintype "passive"))
      (node (ref "U6") (pin "M15") (pinfunction "PB12_M15") (pintype "passive"))
    )
    (net (code "147") (name "Net-(U6A-PB13)") (class "Default")
      (node (ref "R32") (pin "2") (pinfunction "2_2") (pintype "passive"))
      (node (ref "U6") (pin "L15") (pinfunction "PB13_L15") (pintype "passive"))
    )
    (net (code "148") (name "Net-(U6A-PD4)") (class "Default")
      (node (ref "R99") (pin "1") (pinfunction "1_1") (pintype "passive"))
      (node (ref "U6") (pin "C9") (pinfunction "PD4_C9") (pintype "passive"))
    )
    (net (code "149") (name "Net-(U6A-PD5)") (class "Default")
      (node (ref "R96") (pin "1") (pinfunction "1_1") (pintype "passive"))
      (node (ref "U6") (pin "B9") (pinfunction "PD5_B9") (pintype "passive"))
    )
    (net (code "150") (name "Net-(U6A-PD7)") (class "Default")
      (node (ref "R87") (pin "1") (pinfunction "1_1") (pintype "passive"))
      (node (ref "U6") (pin "B8") (pinfunction "PD7_B8") (pintype "passive"))
    )
    (net (code "151") (name "Net-(U6A-PD11)") (class "Default")
      (node (ref "R95") (pin "1") (pinfunction "1_1") (pintype "passive"))
      (node (ref "U6") (pin "J13") (pinfunction "PD11_J13") (pintype "passive"))
    )
    (net (code "152") (name "Net-(U6A-PD12)") (class "Default")
      (node (ref "R91") (pin "1") (pinfunction "1_1") (pintype "passive"))
      (node (ref "U6") (pin "J15") (pinfunction "PD12_J15") (pintype "passive"))
    )
    (net (code "153") (name "Net-(U6A-PD13)") (class "Default")
      (node (ref "R98") (pin "1") (pinfunction "1_1") (pintype "passive"))
      (node (ref "U6") (pin "H15") (pinfunction "PD13_H15") (pintype "passive"))
    )
    (net (code "154") (name "Net-(U6B-BOOT0)") (class "Default")
      (node (ref "R149") (pin "1") (pinfunction "1_1") (pintype "passive"))
      (node (ref "U6") (pin "C5") (pinfunction "BOOT0_C5") (pintype "passive"))
    )
    (net (code "155") (name "Net-(U6B-PA0_C)") (class "Default")
      (node (ref "SB4") (pin "2") (pinfunction "2_2") (pintype "passive"))
      (node (ref "SB5") (pin "2") (pinfunction "2_2") (pintype "passive"))
      (node (ref "U6") (pin "R3") (pinfunction "PA0_C_R3") (pintype "passive"))
    )
    (net (code "156") (name "Net-(U6B-PC2_C)") (class "Default")
      (node (ref "SB41") (pin "1") (pinfunction "1_1") (pintype "passive"))
      (node (ref "SB42") (pin "1") (pinfunction "1_1") (pintype "passive"))
      (node (ref "U6") (pin "N1") (pinfunction "PC2_C_N1") (pintype "passive"))
    )
    (net (code "157") (name "Net-(U6B-PDR_ON)") (class "Default")
      (node (ref "R63") (pin "2") (pinfunction "2_2") (pintype "passive"))
      (node (ref "R64") (pin "2") (pinfunction "2_2") (pintype "passive"))
      (node (ref "U6") (pin "D4") (pinfunction "PDR_ON_D4") (pintype "passive"))
    )
    (net (code "158") (name "Net-(U6B-PE2)") (class "Default")
      (node (ref "R100") (pin "2") (pinfunction "2_2") (pintype "passive"))
      (node (ref "U6") (pin "C3") (pinfunction "PE2_C3") (pintype "passive"))
    )
    (net (code "159") (name "Net-(U6B-PF0)") (class "Default")
      (node (ref "R37") (pin "2") (pinfunction "2_2") (pintype "passive"))
      (node (ref "U6") (pin "F4") (pinfunction "PF0_F4") (pintype "passive"))
    )
    (net (code "160") (name "Net-(U6B-PF1)") (class "Default")
      (node (ref "R46") (pin "2") (pinfunction "2_2") (pintype "passive"))
      (node (ref "U6") (pin "F3") (pinfunction "PF1_F3") (pintype "passive"))
    )
    (net (code "161") (name "Net-(U6B-PF2)") (class "Default")
      (node (ref "R52") (pin "2") (pinfunction "2_2") (pintype "passive"))
      (node (ref "U6") (pin "G3") (pinfunction "PF2_G3") (pintype "passive"))
    )
    (net (code "162") (name "Net-(U6B-PF3)") (class "Default")
      (node (ref "R45") (pin "2") (pinfunction "2_2") (pintype "passive"))
      (node (ref "U6") (pin "H4") (pinfunction "PF3_H4") (pintype "passive"))
    )
    (net (code "163") (name "Net-(U6B-PF4)") (class "Default")
      (node (ref "R60") (pin "2") (pinfunction "2_2") (pintype "passive"))
      (node (ref "U6") (pin "H2") (pinfunction "PF4_H2") (pintype "passive"))
    )
    (net (code "164") (name "Net-(U6B-PF10)") (class "Default")
      (node (ref "R83") (pin "2") (pinfunction "2_2") (pintype "passive"))
      (node (ref "U6") (pin "K3") (pinfunction "PF10_K3") (pintype "passive"))
    )
    (net (code "165") (name "Net-(U6B-PF12)") (class "Default")
      (node (ref "R53") (pin "2") (pinfunction "2_2") (pintype "passive"))
      (node (ref "U6") (pin "P11") (pinfunction "PF12_P11") (pintype "passive"))
    )
    (net (code "166") (name "Net-(U6B-PG0)") (class "Default")
      (node (ref "R48") (pin "1") (pinfunction "1_1") (pintype "passive"))
      (node (ref "U6") (pin "P8") (pinfunction "PG0_P8") (pintype "passive"))
    )
    (net (code "167") (name "Net-(U6B-PG1)") (class "Default")
      (node (ref "R38") (pin "1") (pinfunction "1_1") (pintype "passive"))
      (node (ref "U6") (pin "N9") (pinfunction "PG1_N9") (pintype "passive"))
    )
    (net (code "168") (name "Net-(U6B-PG6)") (class "Default")
      (node (ref "R82") (pin "1") (pinfunction "1_1") (pintype "passive"))
      (node (ref "U6") (pin "F14") (pinfunction "PG6_F14") (pintype "passive"))
    )
    (net (code "169") (name "Net-(U6B-PG9)") (class "Default")
      (node (ref "R93") (pin "1") (pinfunction "1_1") (pintype "passive"))
      (node (ref "U6") (pin "A8") (pinfunction "PG9_A8") (pintype "passive"))
    )
    (net (code "170") (name "Net-(U6B-PG10)") (class "Default")
      (node (ref "R39") (pin "1") (pinfunction "1_1") (pintype "passive"))
      (node (ref "U6") (pin "C8") (pinfunction "PG10_C8") (pintype "passive"))
    )
    (net (code "171") (name "Net-(U6B-PG11)") (class "Default")
      (node (ref "R40") (pin "1") (pinfunction "1_1") (pintype "passive"))
      (node (ref "U6") (pin "A7") (pinfunction "PG11_A7") (pintype "passive"))
    )
    (net (code "172") (name "Net-(U6B-PG12)") (class "Default")
      (node (ref "R66") (pin "1") (pinfunction "1_1") (pintype "passive"))
      (node (ref "U6") (pin "D8") (pinfunction "PG12_D8") (pintype "passive"))
    )
    (net (code "173") (name "Net-(U6B-PH0)") (class "Default")
      (node (ref "R36") (pin "2") (pinfunction "2_2") (pintype "passive"))
      (node (ref "U6") (pin "J1") (pinfunction "PH0_J1") (pintype "passive"))
    )
    (net (code "174") (name "Net-(X1-EN)") (class "Default")
      (node (ref "R41") (pin "1") (pinfunction "1_1") (pintype "passive"))
      (node (ref "X1") (pin "1") (pinfunction "EN_1") (pintype "passive"))
    )
    (net (code "175") (name "Net-(X1-OUT)") (class "Default")
      (node (ref "R35") (pin "2") (pinfunction "2_2") (pintype "passive"))
      (node (ref "R36") (pin "1") (pinfunction "1_1") (pintype "passive"))
      (node (ref "X1") (pin "3") (pinfunction "OUT_3") (pintype "passive"))
    )
    (net (code "176") (name "Net-(X2-X1)") (class "Default")
      (node (ref "C45") (pin "2") (pinfunction "2_2") (pintype "passive"))
      (node (ref "R54") (pin "2") (pinfunction "2_2") (pintype "passive"))
      (node (ref "X2") (pin "1") (pinfunction "X1_1") (pintype "passive"))
    )
    (net (code "177") (name "Net-(X2-X2)") (class "Default")
      (node (ref "C48") (pin "2") (pinfunction "2_2") (pintype "passive"))
      (node (ref "R62") (pin "2") (pinfunction "2_2") (pintype "passive"))
      (node (ref "X2") (pin "2") (pinfunction "X2_2") (pintype "passive"))
    )
    (net (code "178") (name "USB_FS_VBUS") (class "Default")
      (node (ref "U6") (pin "D13") (pinfunction "PA9_D13") (pintype "passive"))
    )
  )
)
